# jlink_main.net
KiCad netlist of a schematic drawn in Altium Designer
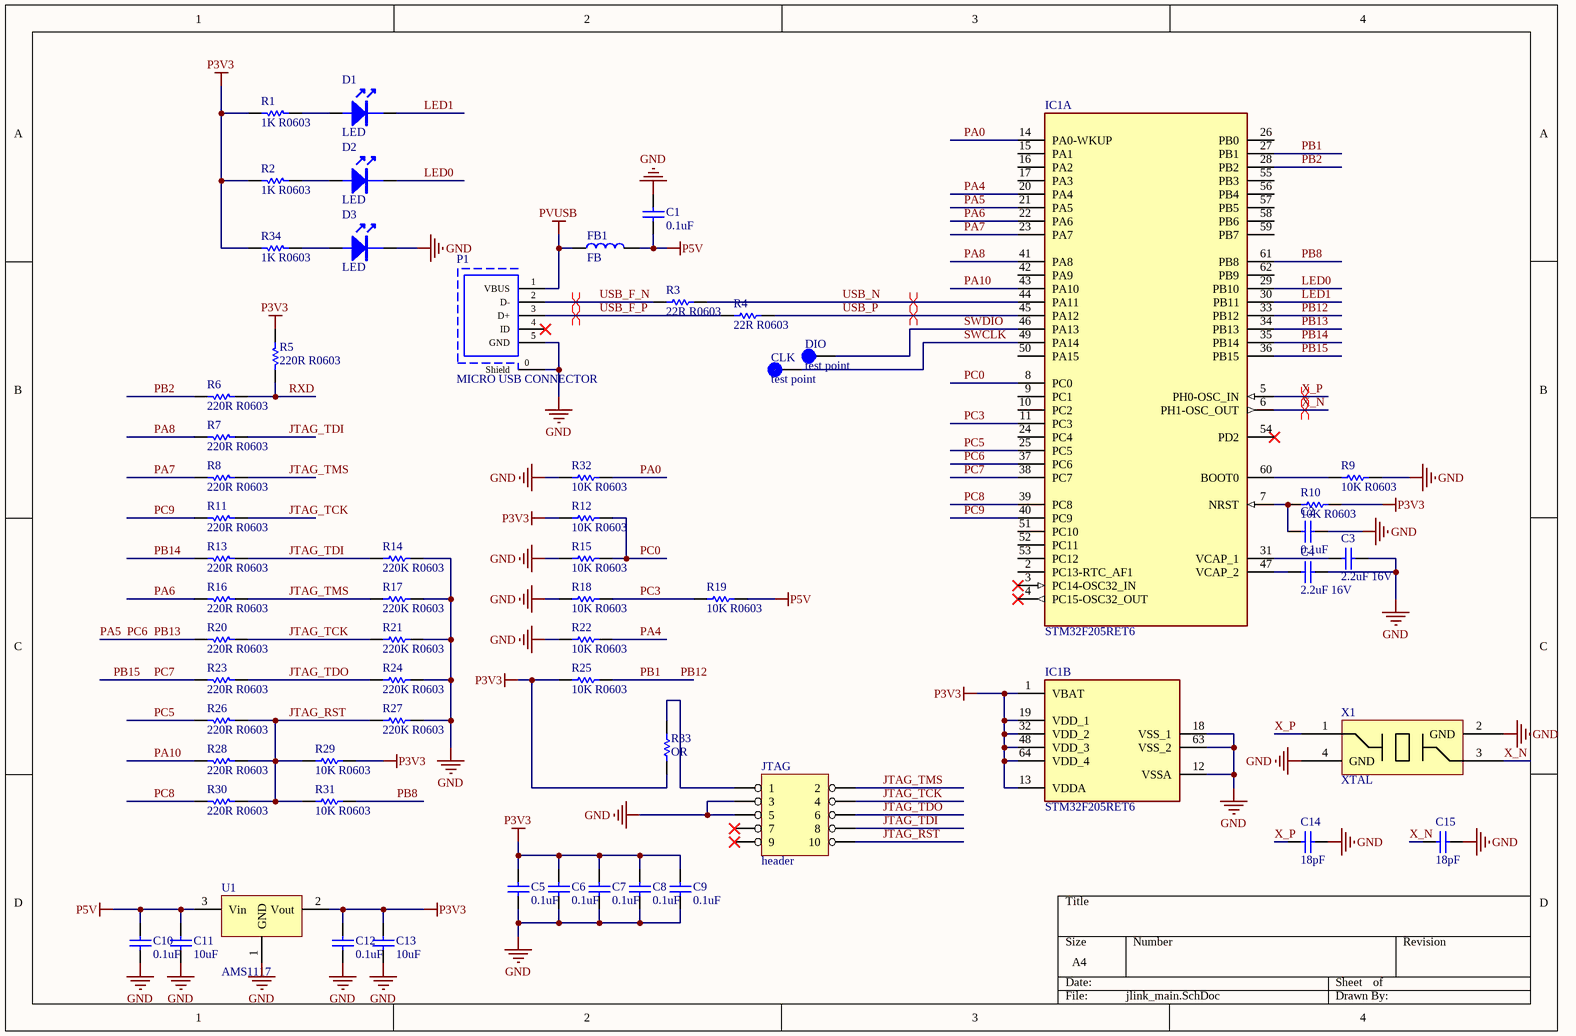
[diagram p0: jlink_main.SchDoc]

(export (version "E")
  (design (tool "Eeschema 10.0.6"))
  (components
    (comp (ref "C1")
      (value "0.1uF")
      (footprint "0603_C")
      (description "Capacitor")
      (fields (field (name "PUBLISHER") "Altium Limited"))
      (libsource (lib "My Footprint") (part "CAP"))
    )
    (comp (ref "C2")
      (value "0.1uF")
      (footprint "0603_C")
      (description "Capacitor")
      (fields (field (name "PUBLISHER") "Altium Limited"))
      (libsource (lib "My Footprint") (part "CAP"))
    )
    (comp (ref "C3")
      (value "2.2uF 16V")
      (footprint "0603_C")
      (description "Capacitor")
      (fields (field (name "PUBLISHER") "Altium Limited"))
      (libsource (lib "My Footprint") (part "CAP"))
    )
    (comp (ref "C4")
      (value "2.2uF 16V")
      (footprint "0603_C")
      (description "Capacitor")
      (fields (field (name "PUBLISHER") "Altium Limited"))
      (libsource (lib "My Footprint") (part "CAP"))
    )
    (comp (ref "C5")
      (value "0.1uF")
      (footprint "0603_C")
      (description "Capacitor")
      (fields (field (name "PUBLISHER") "Altium Limited"))
      (libsource (lib "My Footprint") (part "CAP"))
    )
    (comp (ref "C6")
      (value "0.1uF")
      (footprint "0603_C")
      (description "Capacitor")
      (fields (field (name "PUBLISHER") "Altium Limited"))
      (libsource (lib "My Footprint") (part "CAP"))
    )
    (comp (ref "C7")
      (value "0.1uF")
      (footprint "0603_C")
      (description "Capacitor")
      (fields (field (name "PUBLISHER") "Altium Limited"))
      (libsource (lib "My Footprint") (part "CAP"))
    )
    (comp (ref "C8")
      (value "0.1uF")
      (footprint "0603_C")
      (description "Capacitor")
      (fields (field (name "PUBLISHER") "Altium Limited"))
      (libsource (lib "My Footprint") (part "CAP"))
    )
    (comp (ref "C9")
      (value "0.1uF")
      (footprint "0603_C")
      (description "Capacitor")
      (fields (field (name "PUBLISHER") "Altium Limited"))
      (libsource (lib "My Footprint") (part "CAP"))
    )
    (comp (ref "C10")
      (value "0.1uF")
      (footprint "0603_C")
      (description "Capacitor")
      (fields (field (name "PUBLISHER") "Altium Limited"))
      (libsource (lib "My Footprint") (part "CAP"))
    )
    (comp (ref "C11")
      (value "10uF")
      (footprint "0805_c")
      (description "Capacitor")
      (fields (field (name "PUBLISHER") "Altium Limited"))
      (libsource (lib "My Footprint") (part "CAP"))
    )
    (comp (ref "C12")
      (value "0.1uF")
      (footprint "0603_C")
      (description "Capacitor")
      (fields (field (name "PUBLISHER") "Altium Limited"))
      (libsource (lib "My Footprint") (part "CAP"))
    )
    (comp (ref "C13")
      (value "10uF")
      (footprint "0805_c")
      (description "Capacitor")
      (fields (field (name "PUBLISHER") "Altium Limited"))
      (libsource (lib "My Footprint") (part "CAP"))
    )
    (comp (ref "C14")
      (value "18pF")
      (footprint "0603_C")
      (description "Capacitor")
      (fields (field (name "PUBLISHER") "Altium Limited"))
      (libsource (lib "My Footprint") (part "CAP"))
    )
    (comp (ref "C15")
      (value "18pF")
      (footprint "0603_C")
      (description "Capacitor")
      (fields (field (name "PUBLISHER") "Altium Limited"))
      (libsource (lib "My Footprint") (part "CAP"))
    )
    (comp (ref "CLK")
      (value "test point")
      (footprint "TESTPOINT")
      (libsource (lib "SamacSys") (part "TESTPOINT"))
    )
    (comp (ref "D1")
      (value "LED")
      (footprint "0603_LED")
      (description "LED 发光二极管")
      (libsource (lib "My Footprint") (part "LED"))
    )
    (comp (ref "D2")
      (value "LED")
      (footprint "0603_LED")
      (description "LED 发光二极管")
      (libsource (lib "My Footprint") (part "LED"))
    )
    (comp (ref "D3")
      (value "LED")
      (footprint "0603_LED")
      (description "LED 发光二极管")
      (libsource (lib "My Footprint") (part "LED"))
    )
    (comp (ref "DIO")
      (value "test point")
      (footprint "TESTPOINT")
      (libsource (lib "SamacSys") (part "TESTPOINT"))
    )
    (comp (ref "FB1")
      (value "FB")
      (footprint "FB0603")
      (description "磁珠")
      (libsource (lib "My Footprint") (part "FB"))
    )
    (comp (ref "IC1")
      (value "STM32F205RET6")
      (footprint "QFP50P1200X1200X160-64N")
      (description "Integrated Circuit")
      (fields (field (name "MOUSER PART NUMBER") "511-STM32F205RET6"))
      (libsource (lib "SamacSys") (part "STM32F205RET6"))
    )
    (comp (ref "JTAG")
      (value "header")
      (footprint "header2X5")
      (libsource (lib "My Footprint") (part "HEADER 5X2"))
    )
    (comp (ref "P1")
      (value "MICRO USB CONNECTOR")
      (footprint "USB_Micro_qian")
      (libsource (lib "My Footprint") (part "MICRO USB_in"))
    )
    (comp (ref "R1")
      (value "1K R0603")
      (footprint "0603_R")
      (description "Resistor")
      (fields (field (name "PUBLISHER") "Altium Limited"))
      (libsource (lib "My Footprint") (part "RES"))
    )
    (comp (ref "R2")
      (value "1K R0603")
      (footprint "0603_R")
      (description "Resistor")
      (fields (field (name "PUBLISHER") "Altium Limited"))
      (libsource (lib "My Footprint") (part "RES"))
    )
    (comp (ref "R3")
      (value "22R R0603")
      (footprint "0603_R")
      (description "Resistor")
      (fields (field (name "PUBLISHER") "Altium Limited"))
      (libsource (lib "My Footprint") (part "RES"))
    )
    (comp (ref "R4")
      (value "22R R0603")
      (footprint "0603_R")
      (description "Resistor")
      (fields (field (name "PUBLISHER") "Altium Limited"))
      (libsource (lib "My Footprint") (part "RES"))
    )
    (comp (ref "R5")
      (value "220R R0603")
      (footprint "0603_R")
      (description "Resistor")
      (fields (field (name "PUBLISHER") "Altium Limited"))
      (libsource (lib "My Footprint") (part "RES"))
    )
    (comp (ref "R6")
      (value "220R R0603")
      (footprint "0603_R")
      (description "Resistor")
      (fields (field (name "PUBLISHER") "Altium Limited"))
      (libsource (lib "My Footprint") (part "RES"))
    )
    (comp (ref "R7")
      (value "220R R0603")
      (footprint "0603_R")
      (description "Resistor")
      (fields (field (name "PUBLISHER") "Altium Limited"))
      (libsource (lib "My Footprint") (part "RES"))
    )
    (comp (ref "R8")
      (value "220R R0603")
      (footprint "0603_R")
      (description "Resistor")
      (fields (field (name "PUBLISHER") "Altium Limited"))
      (libsource (lib "My Footprint") (part "RES"))
    )
    (comp (ref "R9")
      (value "10K R0603")
      (footprint "0603_R")
      (description "Resistor")
      (fields (field (name "PUBLISHER") "Altium Limited"))
      (libsource (lib "My Footprint") (part "RES"))
    )
    (comp (ref "R10")
      (value "10K R0603")
      (footprint "0603_R")
      (description "Resistor")
      (fields (field (name "PUBLISHER") "Altium Limited"))
      (libsource (lib "My Footprint") (part "RES"))
    )
    (comp (ref "R11")
      (value "220R R0603")
      (footprint "0603_R")
      (description "Resistor")
      (fields (field (name "PUBLISHER") "Altium Limited"))
      (libsource (lib "My Footprint") (part "RES"))
    )
    (comp (ref "R12")
      (value "10K R0603")
      (footprint "0603_R")
      (description "Resistor")
      (fields (field (name "PUBLISHER") "Altium Limited"))
      (libsource (lib "My Footprint") (part "RES"))
    )
    (comp (ref "R13")
      (value "220R R0603")
      (footprint "0603_R")
      (description "Resistor")
      (fields (field (name "PUBLISHER") "Altium Limited"))
      (libsource (lib "My Footprint") (part "RES"))
    )
    (comp (ref "R14")
      (value "220K R0603")
      (footprint "0603_R")
      (description "Resistor")
      (fields (field (name "PUBLISHER") "Altium Limited"))
      (libsource (lib "My Footprint") (part "RES"))
    )
    (comp (ref "R15")
      (value "10K R0603")
      (footprint "0603_R")
      (description "Resistor")
      (fields (field (name "PUBLISHER") "Altium Limited"))
      (libsource (lib "My Footprint") (part "RES"))
    )
    (comp (ref "R16")
      (value "220R R0603")
      (footprint "0603_R")
      (description "Resistor")
      (fields (field (name "PUBLISHER") "Altium Limited"))
      (libsource (lib "My Footprint") (part "RES"))
    )
    (comp (ref "R17")
      (value "220K R0603")
      (footprint "0603_R")
      (description "Resistor")
      (fields (field (name "PUBLISHER") "Altium Limited"))
      (libsource (lib "My Footprint") (part "RES"))
    )
    (comp (ref "R18")
      (value "10K R0603")
      (footprint "0603_R")
      (description "Resistor")
      (fields (field (name "PUBLISHER") "Altium Limited"))
      (libsource (lib "My Footprint") (part "RES"))
    )
    (comp (ref "R19")
      (value "10K R0603")
      (footprint "0603_R")
      (description "Resistor")
      (fields (field (name "PUBLISHER") "Altium Limited"))
      (libsource (lib "My Footprint") (part "RES"))
    )
    (comp (ref "R20")
      (value "220R R0603")
      (footprint "0603_R")
      (description "Resistor")
      (fields (field (name "PUBLISHER") "Altium Limited"))
      (libsource (lib "My Footprint") (part "RES"))
    )
    (comp (ref "R21")
      (value "220K R0603")
      (footprint "0603_R")
      (description "Resistor")
      (fields (field (name "PUBLISHER") "Altium Limited"))
      (libsource (lib "My Footprint") (part "RES"))
    )
    (comp (ref "R22")
      (value "10K R0603")
      (footprint "0603_R")
      (description "Resistor")
      (fields (field (name "PUBLISHER") "Altium Limited"))
      (libsource (lib "My Footprint") (part "RES"))
    )
    (comp (ref "R23")
      (value "220R R0603")
      (footprint "0603_R")
      (description "Resistor")
      (fields (field (name "PUBLISHER") "Altium Limited"))
      (libsource (lib "My Footprint") (part "RES"))
    )
    (comp (ref "R24")
      (value "220K R0603")
      (footprint "0603_R")
      (description "Resistor")
      (fields (field (name "PUBLISHER") "Altium Limited"))
      (libsource (lib "My Footprint") (part "RES"))
    )
    (comp (ref "R25")
      (value "10K R0603")
      (footprint "0603_R")
      (description "Resistor")
      (fields (field (name "PUBLISHER") "Altium Limited"))
      (libsource (lib "My Footprint") (part "RES"))
    )
    (comp (ref "R26")
      (value "220R R0603")
      (footprint "0603_R")
      (description "Resistor")
      (fields (field (name "PUBLISHER") "Altium Limited"))
      (libsource (lib "My Footprint") (part "RES"))
    )
    (comp (ref "R27")
      (value "220K R0603")
      (footprint "0603_R")
      (description "Resistor")
      (fields (field (name "PUBLISHER") "Altium Limited"))
      (libsource (lib "My Footprint") (part "RES"))
    )
    (comp (ref "R28")
      (value "220R R0603")
      (footprint "0603_R")
      (description "Resistor")
      (fields (field (name "PUBLISHER") "Altium Limited"))
      (libsource (lib "My Footprint") (part "RES"))
    )
    (comp (ref "R29")
      (value "10K R0603")
      (footprint "0603_R")
      (description "Resistor")
      (fields (field (name "PUBLISHER") "Altium Limited"))
      (libsource (lib "My Footprint") (part "RES"))
    )
    (comp (ref "R30")
      (value "220R R0603")
      (footprint "0603_R")
      (description "Resistor")
      (fields (field (name "PUBLISHER") "Altium Limited"))
      (libsource (lib "My Footprint") (part "RES"))
    )
    (comp (ref "R31")
      (value "10K R0603")
      (footprint "0603_R")
      (description "Resistor")
      (fields (field (name "PUBLISHER") "Altium Limited"))
      (libsource (lib "My Footprint") (part "RES"))
    )
    (comp (ref "R32")
      (value "10K R0603")
      (footprint "0603_R")
      (description "Resistor")
      (fields (field (name "PUBLISHER") "Altium Limited"))
      (libsource (lib "My Footprint") (part "RES"))
    )
    (comp (ref "R33")
      (value "OR")
      (footprint "0603_R")
      (description "Resistor")
      (fields (field (name "PUBLISHER") "Altium Limited"))
      (libsource (lib "My Footprint") (part "RES"))
    )
    (comp (ref "R34")
      (value "1K R0603")
      (footprint "0603_R")
      (description "Resistor")
      (fields (field (name "PUBLISHER") "Altium Limited"))
      (libsource (lib "My Footprint") (part "RES"))
    )
    (comp (ref "U1")
      (value "AMS1117")
      (footprint "SOT-223")
      (description "3.3V电压转换器AMS1117")
      (libsource (lib "My Footprint") (part "AMS1117"))
    )
    (comp (ref "X1")
      (value "XTAL")
      (footprint "OSC_KH3225_4P")
      (libsource (lib "My Footprint") (part "XTAL_SMT"))
    )
  )
  (nets
    (net (code "1") (name "/JTAG_RST") (class "Default")
      (node (ref "JTAG") (pin "10") (pinfunction "10_10") (pintype "passive"))
      (node (ref "R26") (pin "1") (pinfunction "1_1") (pintype "passive"))
      (node (ref "R27") (pin "1") (pinfunction "1_1") (pintype "passive"))
      (node (ref "R28") (pin "1") (pinfunction "1_1") (pintype "passive"))
      (node (ref "R29") (pin "1") (pinfunction "1_1") (pintype "passive"))
      (node (ref "R30") (pin "1") (pinfunction "1_1") (pintype "passive"))
      (node (ref "R31") (pin "1") (pinfunction "1_1") (pintype "passive"))
    )
    (net (code "2") (name "/JTAG_TCK") (class "Default")
      (node (ref "JTAG") (pin "4") (pinfunction "4_4") (pintype "passive"))
      (node (ref "R11") (pin "1") (pinfunction "1_1") (pintype "passive"))
      (node (ref "R20") (pin "1") (pinfunction "1_1") (pintype "passive"))
      (node (ref "R21") (pin "1") (pinfunction "1_1") (pintype "passive"))
    )
    (net (code "3") (name "/JTAG_TDI") (class "Default")
      (node (ref "JTAG") (pin "8") (pinfunction "8_8") (pintype "passive"))
      (node (ref "R13") (pin "1") (pinfunction "1_1") (pintype "passive"))
      (node (ref "R14") (pin "1") (pinfunction "1_1") (pintype "passive"))
      (node (ref "R7") (pin "1") (pinfunction "1_1") (pintype "passive"))
    )
    (net (code "4") (name "/JTAG_TDO") (class "Default")
      (node (ref "JTAG") (pin "6") (pinfunction "6_6") (pintype "passive"))
      (node (ref "R23") (pin "1") (pinfunction "1_1") (pintype "passive"))
      (node (ref "R24") (pin "1") (pinfunction "1_1") (pintype "passive"))
    )
    (net (code "5") (name "/JTAG_TMS") (class "Default")
      (node (ref "JTAG") (pin "2") (pinfunction "2_2") (pintype "passive"))
      (node (ref "R16") (pin "1") (pinfunction "1_1") (pintype "passive"))
      (node (ref "R17") (pin "1") (pinfunction "1_1") (pintype "passive"))
      (node (ref "R8") (pin "1") (pinfunction "1_1") (pintype "passive"))
    )
    (net (code "6") (name "/LED0") (class "Default")
      (node (ref "D2") (pin "2") (pinfunction "K_2") (pintype "passive"))
      (node (ref "IC1") (pin "29") (pinfunction "PB10_29") (pintype "passive"))
    )
    (net (code "7") (name "/LED1") (class "Default")
      (node (ref "D1") (pin "2") (pinfunction "K_2") (pintype "passive"))
      (node (ref "IC1") (pin "30") (pinfunction "PB11_30") (pintype "passive"))
    )
    (net (code "8") (name "/PA0") (class "Default")
      (node (ref "IC1") (pin "14") (pinfunction "PA0-WKUP_14") (pintype "passive"))
      (node (ref "R32") (pin "2") (pinfunction "2_2") (pintype "passive"))
    )
    (net (code "9") (name "/PA4") (class "Default")
      (node (ref "IC1") (pin "20") (pinfunction "PA4_20") (pintype "passive"))
      (node (ref "R22") (pin "2") (pinfunction "2_2") (pintype "passive"))
    )
    (net (code "10") (name "/PA5") (class "Default")
      (node (ref "IC1") (pin "21") (pinfunction "PA5_21") (pintype "passive"))
      (node (ref "IC1") (pin "34") (pinfunction "PB13_34") (pintype "passive"))
      (node (ref "IC1") (pin "37") (pinfunction "PC6_37") (pintype "passive"))
      (node (ref "R20") (pin "2") (pinfunction "2_2") (pintype "passive"))
    )
    (net (code "11") (name "/PA6") (class "Default")
      (node (ref "IC1") (pin "22") (pinfunction "PA6_22") (pintype "passive"))
      (node (ref "R16") (pin "2") (pinfunction "2_2") (pintype "passive"))
    )
    (net (code "12") (name "/PA7") (class "Default")
      (node (ref "IC1") (pin "23") (pinfunction "PA7_23") (pintype "passive"))
      (node (ref "R8") (pin "2") (pinfunction "2_2") (pintype "passive"))
    )
    (net (code "13") (name "/PA8") (class "Default")
      (node (ref "IC1") (pin "41") (pinfunction "PA8_41") (pintype "passive"))
      (node (ref "R7") (pin "2") (pinfunction "2_2") (pintype "passive"))
    )
    (net (code "14") (name "/PA10") (class "Default")
      (node (ref "IC1") (pin "43") (pinfunction "PA10_43") (pintype "passive"))
      (node (ref "R28") (pin "2") (pinfunction "2_2") (pintype "passive"))
    )
    (net (code "15") (name "/PB1") (class "Default")
      (node (ref "IC1") (pin "27") (pinfunction "PB1_27") (pintype "passive"))
      (node (ref "IC1") (pin "33") (pinfunction "PB12_33") (pintype "passive"))
      (node (ref "R25") (pin "2") (pinfunction "2_2") (pintype "passive"))
    )
    (net (code "16") (name "/PB2") (class "Default")
      (node (ref "IC1") (pin "28") (pinfunction "PB2_28") (pintype "passive"))
      (node (ref "R6") (pin "2") (pinfunction "2_2") (pintype "passive"))
    )
    (net (code "17") (name "/PB8") (class "Default")
      (node (ref "IC1") (pin "61") (pinfunction "PB8_61") (pintype "passive"))
      (node (ref "R31") (pin "2") (pinfunction "2_2") (pintype "passive"))
    )
    (net (code "18") (name "/PB14") (class "Default")
      (node (ref "IC1") (pin "35") (pinfunction "PB14_35") (pintype "passive"))
      (node (ref "R13") (pin "2") (pinfunction "2_2") (pintype "passive"))
    )
    (net (code "19") (name "/PB15") (class "Default")
      (node (ref "IC1") (pin "36") (pinfunction "PB15_36") (pintype "passive"))
      (node (ref "IC1") (pin "38") (pinfunction "PC7_38") (pintype "passive"))
      (node (ref "R23") (pin "2") (pinfunction "2_2") (pintype "passive"))
    )
    (net (code "20") (name "/PC0") (class "Default")
      (node (ref "IC1") (pin "8") (pinfunction "PC0_8") (pintype "passive"))
      (node (ref "R12") (pin "2") (pinfunction "2_2") (pintype "passive"))
      (node (ref "R15") (pin "2") (pinfunction "2_2") (pintype "passive"))
    )
    (net (code "21") (name "/PC3") (class "Default")
      (node (ref "IC1") (pin "11") (pinfunction "PC3_11") (pintype "passive"))
      (node (ref "R18") (pin "2") (pinfunction "2_2") (pintype "passive"))
      (node (ref "R19") (pin "1") (pinfunction "1_1") (pintype "passive"))
    )
    (net (code "22") (name "/PC5") (class "Default")
      (node (ref "IC1") (pin "25") (pinfunction "PC5_25") (pintype "passive"))
      (node (ref "R26") (pin "2") (pinfunction "2_2") (pintype "passive"))
    )
    (net (code "23") (name "/PC8") (class "Default")
      (node (ref "IC1") (pin "39") (pinfunction "PC8_39") (pintype "passive"))
      (node (ref "R30") (pin "2") (pinfunction "2_2") (pintype "passive"))
    )
    (net (code "24") (name "/PC9") (class "Default")
      (node (ref "IC1") (pin "40") (pinfunction "PC9_40") (pintype "passive"))
      (node (ref "R11") (pin "2") (pinfunction "2_2") (pintype "passive"))
    )
    (net (code "25") (name "/RXD") (class "Default")
      (node (ref "R5") (pin "2") (pinfunction "2_2") (pintype "passive"))
      (node (ref "R6") (pin "1") (pinfunction "1_1") (pintype "passive"))
    )
    (net (code "26") (name "/SWCLK") (class "Default")
      (node (ref "CLK") (pin "1") (pinfunction "TP_1") (pintype "passive"))
      (node (ref "IC1") (pin "49") (pinfunction "PA14_49") (pintype "passive"))
    )
    (net (code "27") (name "/SWDIO") (class "Default")
      (node (ref "DIO") (pin "1") (pinfunction "TP_1") (pintype "passive"))
      (node (ref "IC1") (pin "46") (pinfunction "PA13_46") (pintype "passive"))
    )
    (net (code "28") (name "/USB_F_N") (class "Default")
      (node (ref "P1") (pin "2") (pinfunction "D-_2") (pintype "passive"))
      (node (ref "R3") (pin "1") (pinfunction "1_1") (pintype "passive"))
    )
    (net (code "29") (name "/USB_F_P") (class "Default")
      (node (ref "P1") (pin "3") (pinfunction "D+_3") (pintype "passive"))
      (node (ref "R4") (pin "1") (pinfunction "1_1") (pintype "passive"))
    )
    (net (code "30") (name "/USB_N") (class "Default")
      (node (ref "IC1") (pin "44") (pinfunction "PA11_44") (pintype "passive"))
      (node (ref "R3") (pin "2") (pinfunction "2_2") (pintype "passive"))
    )
    (net (code "31") (name "/USB_P") (class "Default")
      (node (ref "IC1") (pin "45") (pinfunction "PA12_45") (pintype "passive"))
      (node (ref "R4") (pin "2") (pinfunction "2_2") (pintype "passive"))
    )
    (net (code "32") (name "/X_N") (class "Default")
      (node (ref "C15") (pin "1") (pinfunction "1_1") (pintype "passive"))
      (node (ref "IC1") (pin "6") (pinfunction "PH1-OSC_OUT_6") (pintype "output"))
      (node (ref "X1") (pin "3") (pinfunction "OSC2_3") (pintype "passive"))
    )
    (net (code "33") (name "/X_P") (class "Default")
      (node (ref "C14") (pin "2") (pinfunction "2_2") (pintype "passive"))
      (node (ref "IC1") (pin "5") (pinfunction "PH0-OSC_IN_5") (pintype "input"))
      (node (ref "X1") (pin "1") (pinfunction "OSC1_1") (pintype "passive"))
    )
    (net (code "34") (name "GND") (class "Default")
      (node (ref "C1") (pin "2") (pinfunction "2_2") (pintype "passive"))
      (node (ref "C10") (pin "1") (pinfunction "1_1") (pintype "passive"))
      (node (ref "C11") (pin "1") (pinfunction "1_1") (pintype "passive"))
      (node (ref "C12") (pin "1") (pinfunction "1_1") (pintype "passive"))
      (node (ref "C13") (pin "1") (pinfunction "1_1") (pintype "passive"))
      (node (ref "C14") (pin "1") (pinfunction "1_1") (pintype "passive"))
      (node (ref "C15") (pin "2") (pinfunction "2_2") (pintype "passive"))
      (node (ref "C2") (pin "1") (pinfunction "1_1") (pintype "passive"))
      (node (ref "C3") (pin "2") (pinfunction "2_2") (pintype "passive"))
      (node (ref "C4") (pin "2") (pinfunction "2_2") (pintype "passive"))
      (node (ref "C5") (pin "1") (pinfunction "1_1") (pintype "passive"))
      (node (ref "C6") (pin "1") (pinfunction "1_1") (pintype "passive"))
      (node (ref "C7") (pin "1") (pinfunction "1_1") (pintype "passive"))
      (node (ref "C8") (pin "1") (pinfunction "1_1") (pintype "passive"))
      (node (ref "C9") (pin "1") (pinfunction "1_1") (pintype "passive"))
      (node (ref "D3") (pin "2") (pinfunction "K_2") (pintype "passive"))
      (node (ref "IC1") (pin "12") (pinfunction "VSSA_12") (pintype "power_in"))
      (node (ref "IC1") (pin "18") (pinfunction "VSS_1_18") (pintype "power_in"))
      (node (ref "IC1") (pin "63") (pinfunction "VSS_2_63") (pintype "power_in"))
      (node (ref "JTAG") (pin "3") (pinfunction "3_3") (pintype "passive"))
      (node (ref "JTAG") (pin "5") (pinfunction "5_5") (pintype "passive"))
      (node (ref "P1") (pin "0") (pinfunction "Shield_0") (pintype "passive"))
      (node (ref "P1") (pin "5") (pinfunction "GND_5") (pintype "passive"))
      (node (ref "R14") (pin "2") (pinfunction "2_2") (pintype "passive"))
      (node (ref "R15") (pin "1") (pinfunction "1_1") (pintype "passive"))
      (node (ref "R17") (pin "2") (pinfunction "2_2") (pintype "passive"))
      (node (ref "R18") (pin "1") (pinfunction "1_1") (pintype "passive"))
      (node (ref "R21") (pin "2") (pinfunction "2_2") (pintype "passive"))
      (node (ref "R22") (pin "1") (pinfunction "1_1") (pintype "passive"))
      (node (ref "R24") (pin "2") (pinfunction "2_2") (pintype "passive"))
      (node (ref "R27") (pin "2") (pinfunction "2_2") (pintype "passive"))
      (node (ref "R32") (pin "1") (pinfunction "1_1") (pintype "passive"))
      (node (ref "R9") (pin "2") (pinfunction "2_2") (pintype "passive"))
      (node (ref "U1") (pin "1") (pinfunction "GND_1") (pintype "passive"))
      (node (ref "X1") (pin "2") (pinfunction "GND_2") (pintype "passive"))
      (node (ref "X1") (pin "4") (pinfunction "GND_4") (pintype "passive"))
    )
    (net (code "35") (name "Net-(D1-A)") (class "Default")
      (node (ref "D1") (pin "1") (pinfunction "A_1") (pintype "passive"))
      (node (ref "R1") (pin "1") (pinfunction "1_1") (pintype "passive"))
    )
    (net (code "36") (name "Net-(D2-A)") (class "Default")
      (node (ref "D2") (pin "1") (pinfunction "A_1") (pintype "passive"))
      (node (ref "R2") (pin "1") (pinfunction "1_1") (pintype "passive"))
    )
    (net (code "37") (name "Net-(D3-A)") (class "Default")
      (node (ref "D3") (pin "1") (pinfunction "A_1") (pintype "passive"))
      (node (ref "R34") (pin "1") (pinfunction "1_1") (pintype "passive"))
    )
    (net (code "38") (name "Net-(IC1A-BOOT0)") (class "Default")
      (node (ref "IC1") (pin "60") (pinfunction "BOOT0_60") (pintype "passive"))
      (node (ref "R9") (pin "1") (pinfunction "1_1") (pintype "passive"))
    )
    (net (code "39") (name "Net-(IC1A-NRST)") (class "Default")
      (node (ref "C2") (pin "2") (pinfunction "2_2") (pintype "passive"))
      (node (ref "IC1") (pin "7") (pinfunction "NRST_7") (pintype "input"))
      (node (ref "R10") (pin "1") (pinfunction "1_1") (pintype "passive"))
    )
    (net (code "40") (name "Net-(IC1A-VCAP_1)") (class "Default")
      (node (ref "C3") (pin "1") (pinfunction "1_1") (pintype "passive"))
      (node (ref "IC1") (pin "31") (pinfunction "VCAP_1_31") (pintype "passive"))
    )
    (net (code "41") (name "Net-(IC1A-VCAP_2)") (class "Default")
      (node (ref "C4") (pin "1") (pinfunction "1_1") (pintype "passive"))
      (node (ref "IC1") (pin "47") (pinfunction "VCAP_2_47") (pintype "passive"))
    )
    (net (code "42") (name "Net-(JTAG-Pad1)") (class "Default")
      (node (ref "JTAG") (pin "1") (pinfunction "1_1") (pintype "passive"))
      (node (ref "R33") (pin "2") (pinfunction "2_2") (pintype "passive"))
    )
    (net (code "43") (name "P3V3") (class "Default")
      (node (ref "C12") (pin "2") (pinfunction "2_2") (pintype "passive"))
      (node (ref "C13") (pin "2") (pinfunction "2_2") (pintype "passive"))
      (node (ref "C5") (pin "2") (pinfunction "2_2") (pintype "passive"))
      (node (ref "C6") (pin "2") (pinfunction "2_2") (pintype "passive"))
      (node (ref "C7") (pin "2") (pinfunction "2_2") (pintype "passive"))
      (node (ref "C8") (pin "2") (pinfunction "2_2") (pintype "passive"))
      (node (ref "C9") (pin "2") (pinfunction "2_2") (pintype "passive"))
      (node (ref "IC1") (pin "1") (pinfunction "VBAT_1") (pintype "passive"))
      (node (ref "IC1") (pin "13") (pinfunction "VDDA_13") (pintype "power_in"))
      (node (ref "IC1") (pin "19") (pinfunction "VDD_1_19") (pintype "power_in"))
      (node (ref "IC1") (pin "32") (pinfunction "VDD_2_32") (pintype "power_in"))
      (node (ref "IC1") (pin "48") (pinfunction "VDD_3_48") (pintype "power_in"))
      (node (ref "IC1") (pin "64") (pinfunction "VDD_4_64") (pintype "power_in"))
      (node (ref "R1") (pin "2") (pinfunction "2_2") (pintype "passive"))
      (node (ref "R10") (pin "2") (pinfunction "2_2") (pintype "passive"))
      (node (ref "R12") (pin "1") (pinfunction "1_1") (pintype "passive"))
      (node (ref "R2") (pin "2") (pinfunction "2_2") (pintype "passive"))
      (node (ref "R25") (pin "1") (pinfunction "1_1") (pintype "passive"))
      (node (ref "R29") (pin "2") (pinfunction "2_2") (pintype "passive"))
      (node (ref "R33") (pin "1") (pinfunction "1_1") (pintype "passive"))
      (node (ref "R34") (pin "2") (pinfunction "2_2") (pintype "passive"))
      (node (ref "R5") (pin "1") (pinfunction "1_1") (pintype "passive"))
      (node (ref "U1") (pin "2") (pinfunction "Vout_2") (pintype "passive"))
    )
    (net (code "44") (name "P5V") (class "Default")
      (node (ref "C1") (pin "1") (pinfunction "1_1") (pintype "passive"))
      (node (ref "C10") (pin "2") (pinfunction "2_2") (pintype "passive"))
      (node (ref "C11") (pin "2") (pinfunction "2_2") (pintype "passive"))
      (node (ref "FB1") (pin "2") (pinfunction "2_2") (pintype "passive"))
      (node (ref "R19") (pin "2") (pinfunction "2_2") (pintype "passive"))
      (node (ref "U1") (pin "3") (pinfunction "Vin_3") (pintype "passive"))
    )
    (net (code "45") (name "PVUSB") (class "Default")
      (node (ref "FB1") (pin "1") (pinfunction "1_1") (pintype "passive"))
      (node (ref "P1") (pin "1") (pinfunction "VBUS_1") (pintype "passive"))
    )
    (net (code "46") (name "unconnected-(IC1A-PA1-Pad15)") (class "Default")
      (node (ref "IC1") (pin "15") (pinfunction "PA1_15") (pintype "passive"))
    )
    (net (code "47") (name "unconnected-(IC1A-PA2-Pad16)") (class "Default")
      (node (ref "IC1") (pin "16") (pinfunction "PA2_16") (pintype "passive"))
    )
    (net (code "48") (name "unconnected-(IC1A-PA3-Pad17)") (class "Default")
      (node (ref "IC1") (pin "17") (pinfunction "PA3_17") (pintype "passive"))
    )
    (net (code "49") (name "unconnected-(IC1A-PA9-Pad42)") (class "Default")
      (node (ref "IC1") (pin "42") (pinfunction "PA9_42") (pintype "passive"))
    )
    (net (code "50") (name "unconnected-(IC1A-PA15-Pad50)") (class "Default")
      (node (ref "IC1") (pin "50") (pinfunction "PA15_50") (pintype "passive"))
    )
    (net (code "51") (name "unconnected-(IC1A-PB0-Pad26)") (class "Default")
      (node (ref "IC1") (pin "26") (pinfunction "PB0_26") (pintype "passive"))
    )
    (net (code "52") (name "unconnected-(IC1A-PB3-Pad55)") (class "Default")
      (node (ref "IC1") (pin "55") (pinfunction "PB3_55") (pintype "passive"))
    )
    (net (code "53") (name "unconnected-(IC1A-PB4-Pad56)") (class "Default")
      (node (ref "IC1") (pin "56") (pinfunction "PB4_56") (pintype "passive"))
    )
    (net (code "54") (name "unconnected-(IC1A-PB5-Pad57)") (class "Default")
      (node (ref "IC1") (pin "57") (pinfunction "PB5_57") (pintype "passive"))
    )
    (net (code "55") (name "unconnected-(IC1A-PB6-Pad58)") (class "Default")
      (node (ref "IC1") (pin "58") (pinfunction "PB6_58") (pintype "passive"))
    )
    (net (code "56") (name "unconnected-(IC1A-PB7-Pad59)") (class "Default")
      (node (ref "IC1") (pin "59") (pinfunction "PB7_59") (pintype "passive"))
    )
    (net (code "57") (name "unconnected-(IC1A-PB9-Pad62)") (class "Default")
      (node (ref "IC1") (pin "62") (pinfunction "PB9_62") (pintype "passive"))
    )
    (net (code "58") (name "unconnected-(IC1A-PC1-Pad9)") (class "Default")
      (node (ref "IC1") (pin "9") (pinfunction "PC1_9") (pintype "passive"))
    )
    (net (code "59") (name "unconnected-(IC1A-PC2-Pad10)") (class "Default")
      (node (ref "IC1") (pin "10") (pinfunction "PC2_10") (pintype "passive"))
    )
    (net (code "60") (name "unconnected-(IC1A-PC4-Pad24)") (class "Default")
      (node (ref "IC1") (pin "24") (pinfunction "PC4_24") (pintype "passive"))
    )
    (net (code "61") (name "unconnected-(IC1A-PC10-Pad51)") (class "Default")
      (node (ref "IC1") (pin "51") (pinfunction "PC10_51") (pintype "passive"))
    )
    (net (code "62") (name "unconnected-(IC1A-PC11-Pad52)") (class "Default")
      (node (ref "IC1") (pin "52") (pinfunction "PC11_52") (pintype "passive"))
    )
    (net (code "63") (name "unconnected-(IC1A-PC12-Pad53)") (class "Default")
      (node (ref "IC1") (pin "53") (pinfunction "PC12_53") (pintype "passive"))
    )
    (net (code "64") (name "unconnected-(IC1A-PC13-RTC_AF1-Pad2)") (class "Default")
      (node (ref "IC1") (pin "2") (pinfunction "PC13-RTC_AF1_2") (pintype "passive"))
    )
    (net (code "65") (name "unconnected-(IC1A-PC14-OSC32_IN-Pad3)") (class "Default")
      (node (ref "IC1") (pin "3") (pinfunction "PC14-OSC32_IN_3") (pintype "input+no_connect"))
    )
    (net (code "66") (name "unconnected-(IC1A-PC15-OSC32_OUT-Pad4)") (class "Default")
      (node (ref "IC1") (pin "4") (pinfunction "PC15-OSC32_OUT_4") (pintype "output+no_connect"))
    )
    (net (code "67") (name "unconnected-(IC1A-PD2-Pad54)") (class "Default")
      (node (ref "IC1") (pin "54") (pinfunction "PD2_54") (pintype "passive+no_connect"))
    )
    (net (code "68") (name "unconnected-(JTAG-Pad7)") (class "Default")
      (node (ref "JTAG") (pin "7") (pinfunction "7_7") (pintype "passive+no_connect"))
    )
    (net (code "69") (name "unconnected-(JTAG-Pad9)") (class "Default")
      (node (ref "JTAG") (pin "9") (pinfunction "9_9") (pintype "passive+no_connect"))
    )
    (net (code "70") (name "unconnected-(P1-ID-Pad4)") (class "Default")
      (node (ref "P1") (pin "4") (pinfunction "ID_4") (pintype "passive+no_connect"))
    )
  )
)
